# TS-ARM3_0_7.net
KiCad netlist of a schematic drawn in EAGLE
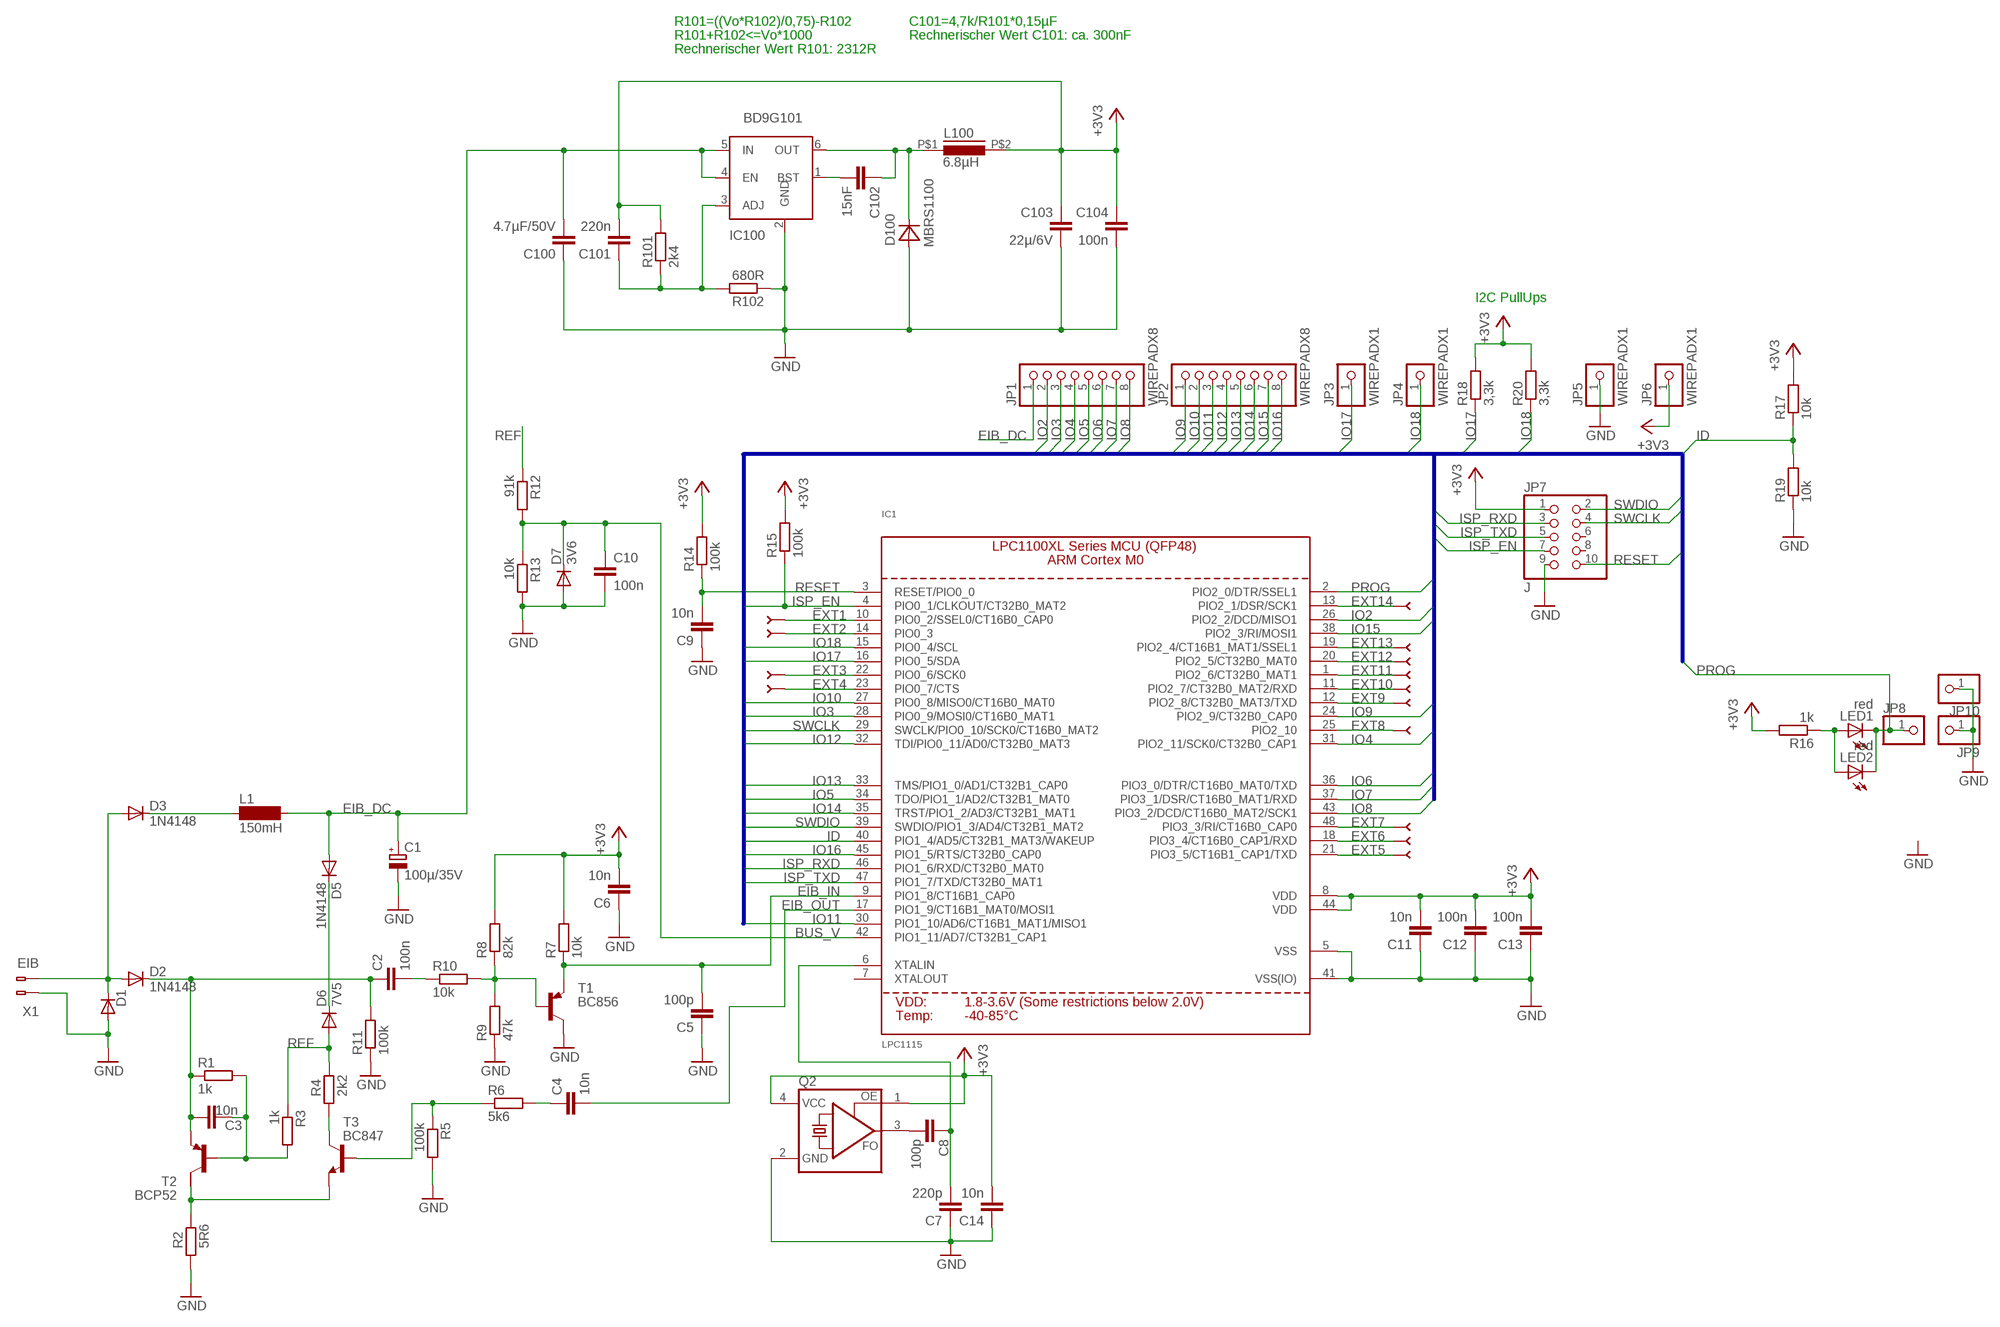
[diagram p0: schematic, sheet 1]

(export (version "E")
  (design (tool "Eeschema 10.0.6"))
  (components
    (comp (ref "C1")
      (value "100µ/35V")
      (footprint "eagle-import:SANYO-OSCON_SMD_C6")
      (libsource (lib "eagle-import") (part "CPOL-EUSANYO_SMD_C6"))
    )
    (comp (ref "C2")
      (value "100n")
      (footprint "eagle-import:C1206")
      (libsource (lib "eagle-import") (part "C-EUC1206"))
    )
    (comp (ref "C3")
      (value "10n")
      (footprint "eagle-import:C1206")
      (libsource (lib "eagle-import") (part "C-EUC1206"))
    )
    (comp (ref "C4")
      (value "10n")
      (footprint "eagle-import:C1206")
      (libsource (lib "eagle-import") (part "C-EUC1206"))
    )
    (comp (ref "C5")
      (value "100p")
      (footprint "eagle-import:C1206")
      (libsource (lib "eagle-import") (part "C-EUC1206"))
    )
    (comp (ref "C6")
      (value "10n")
      (footprint "eagle-import:C1206")
      (libsource (lib "eagle-import") (part "C-EUC1206"))
    )
    (comp (ref "C7")
      (value "220p")
      (footprint "eagle-import:C1206")
      (libsource (lib "eagle-import") (part "C-EUC1206"))
    )
    (comp (ref "C8")
      (value "100p")
      (footprint "eagle-import:C1206")
      (libsource (lib "eagle-import") (part "C-EUC1206"))
    )
    (comp (ref "C9")
      (value "10n")
      (footprint "eagle-import:C1206")
      (libsource (lib "eagle-import") (part "C-EUC1206"))
    )
    (comp (ref "C10")
      (value "100n")
      (footprint "eagle-import:C1206")
      (libsource (lib "eagle-import") (part "C-EUC1206"))
    )
    (comp (ref "C11")
      (value "10n")
      (footprint "eagle-import:C1206")
      (libsource (lib "eagle-import") (part "C-EUC1206"))
    )
    (comp (ref "C12")
      (value "100n")
      (footprint "eagle-import:C1206")
      (libsource (lib "eagle-import") (part "C-EUC1206"))
    )
    (comp (ref "C13")
      (value "100n")
      (footprint "eagle-import:C1206")
      (libsource (lib "eagle-import") (part "C-EUC1206"))
    )
    (comp (ref "C14")
      (value "10n")
      (footprint "eagle-import:C1206")
      (libsource (lib "eagle-import") (part "C-EUC1206"))
    )
    (comp (ref "C100")
      (value "4.7µF/50V")
      (footprint "eagle-import:C1206")
      (libsource (lib "eagle-import") (part "C-EUC1206"))
    )
    (comp (ref "C101")
      (value "220n")
      (footprint "eagle-import:C1206")
      (libsource (lib "eagle-import") (part "C-EUC1206"))
    )
    (comp (ref "C102")
      (value "15nF")
      (footprint "eagle-import:C1206")
      (libsource (lib "eagle-import") (part "C-EUC1206"))
    )
    (comp (ref "C103")
      (value "22µ/6V")
      (footprint "eagle-import:C1206")
      (libsource (lib "eagle-import") (part "C-EUC1206"))
    )
    (comp (ref "C104")
      (value "100n")
      (footprint "eagle-import:C1206")
      (libsource (lib "eagle-import") (part "C-EUC1206"))
    )
    (comp (ref "D1")
      (value "SMAJ40C")
      (footprint "eagle-import:SMB")
      (libsource (lib "eagle-import") (part "D-SMB"))
    )
    (comp (ref "D2")
      (value "1N4148")
      (footprint "eagle-import:MINIMELF")
      (libsource (lib "eagle-import") (part "DIODE-MINIMELF"))
    )
    (comp (ref "D3")
      (value "1N4148")
      (footprint "eagle-import:MINIMELF")
      (libsource (lib "eagle-import") (part "DIODE-MINIMELF"))
    )
    (comp (ref "D5")
      (value "1N4148")
      (footprint "eagle-import:MINIMELF")
      (libsource (lib "eagle-import") (part "DIODE-MINIMELF"))
    )
    (comp (ref "D6")
      (value "7V5")
      (footprint "eagle-import:MINIMELF")
      (libsource (lib "eagle-import") (part "DIODE-MINIMELF"))
    )
    (comp (ref "D7")
      (value "3V6")
      (footprint "eagle-import:MINIMELF")
      (libsource (lib "eagle-import") (part "DIODE-MINIMELF"))
    )
    (comp (ref "D100")
      (value "MBRS1100")
      (footprint "eagle-import:SMA")
      (libsource (lib "eagle-import") (part "MBRA340T3"))
    )
    (comp (ref "IC1")
      (value "LPC1115")
      (footprint "eagle-import:LQFP48")
      (libsource (lib "eagle-import") (part "LPC1113/4/5_QFP48_XLSERIES"))
    )
    (comp (ref "IC100")
      (value "BD9G101")
      (footprint "eagle-import:SOT23-6")
      (libsource (lib "eagle-import") (part "BD9G101GBD9G101G-SOT23-6"))
    )
    (comp (ref "JP1")
      (value "WIREPADX8")
      (footprint "eagle-import:SMD1,27X2,54X8")
      (libsource (lib "eagle-import") (part "WIREPADX8"))
    )
    (comp (ref "JP2")
      (value "WIREPADX8")
      (footprint "eagle-import:SMD1,27X2,54X8")
      (libsource (lib "eagle-import") (part "WIREPADX8"))
    )
    (comp (ref "JP3")
      (value "WIREPADX1")
      (footprint "eagle-import:SMD1,27X2,54")
      (libsource (lib "eagle-import") (part "WIREPADX1"))
    )
    (comp (ref "JP4")
      (value "WIREPADX1")
      (footprint "eagle-import:SMD1,27X2,54")
      (libsource (lib "eagle-import") (part "WIREPADX1"))
    )
    (comp (ref "JP5")
      (value "WIREPADX1")
      (footprint "eagle-import:SMD1,27X2,54")
      (libsource (lib "eagle-import") (part "WIREPADX1"))
    )
    (comp (ref "JP6")
      (value "WIREPADX1")
      (footprint "eagle-import:SMD1,27X2,54")
      (libsource (lib "eagle-import") (part "WIREPADX1"))
    )
    (comp (ref "JP7")
      (value "J")
      (footprint "eagle-import:2X05M")
      (libsource (lib "eagle-import") (part "PINHD-2X05_2.00"))
    )
    (comp (ref "JP8")
      (value "PINHD-1X1")
      (footprint "eagle-import:1X01")
      (libsource (lib "eagle-import") (part "PINHD-1X1"))
    )
    (comp (ref "JP9")
      (value "PINHD-1X1")
      (footprint "eagle-import:1X01")
      (libsource (lib "eagle-import") (part "PINHD-1X1"))
    )
    (comp (ref "JP10")
      (value "PINHD-1X1")
      (footprint "eagle-import:1X01")
      (libsource (lib "eagle-import") (part "PINHD-1X1"))
    )
    (comp (ref "L1")
      (value "150mH")
      (footprint "eagle-import:SD12_1000")
      (libsource (lib "eagle-import") (part "SD12-1000"))
    )
    (comp (ref "L100")
      (value "6.8µH")
      (footprint "eagle-import:PIS2812")
      (libsource (lib "eagle-import") (part "IND_FASTRON_1616FPS"))
    )
    (comp (ref "LED1")
      (value "red")
      (footprint "eagle-import:CHIPLED_1206")
      (libsource (lib "eagle-import") (part "LEDCHIPLED_1206"))
    )
    (comp (ref "LED2")
      (value "red")
      (footprint "eagle-import:LED3MM")
      (libsource (lib "eagle-import") (part "LED3MM"))
    )
    (comp (ref "P1")
      (value "PAD")
      (footprint "eagle-import:PAD")
      (libsource (lib "eagle-import") (part "PAD"))
    )
    (comp (ref "P2")
      (value "PAD")
      (footprint "eagle-import:PAD")
      (libsource (lib "eagle-import") (part "PAD"))
    )
    (comp (ref "P3")
      (value "PAD")
      (footprint "eagle-import:PAD")
      (libsource (lib "eagle-import") (part "PAD"))
    )
    (comp (ref "P4")
      (value "PAD")
      (footprint "eagle-import:PAD")
      (libsource (lib "eagle-import") (part "PAD"))
    )
    (comp (ref "P5")
      (value "PAD")
      (footprint "eagle-import:PAD")
      (libsource (lib "eagle-import") (part "PAD"))
    )
    (comp (ref "P6")
      (value "PAD")
      (footprint "eagle-import:PAD")
      (libsource (lib "eagle-import") (part "PAD"))
    )
    (comp (ref "P7")
      (value "PAD")
      (footprint "eagle-import:PAD")
      (libsource (lib "eagle-import") (part "PAD"))
    )
    (comp (ref "P8")
      (value "PAD")
      (footprint "eagle-import:PAD")
      (libsource (lib "eagle-import") (part "PAD"))
    )
    (comp (ref "P9")
      (value "PAD")
      (footprint "eagle-import:PAD")
      (libsource (lib "eagle-import") (part "PAD"))
    )
    (comp (ref "P10")
      (value "PAD")
      (footprint "eagle-import:PAD")
      (libsource (lib "eagle-import") (part "PAD"))
    )
    (comp (ref "P11")
      (value "PAD")
      (footprint "eagle-import:PAD")
      (libsource (lib "eagle-import") (part "PAD"))
    )
    (comp (ref "P12")
      (value "PAD")
      (footprint "eagle-import:PAD")
      (libsource (lib "eagle-import") (part "PAD"))
    )
    (comp (ref "P13")
      (value "PAD")
      (footprint "eagle-import:PAD")
      (libsource (lib "eagle-import") (part "PAD"))
    )
    (comp (ref "P14")
      (value "PAD")
      (footprint "eagle-import:PAD")
      (libsource (lib "eagle-import") (part "PAD"))
    )
    (comp (ref "Q2")
      (value "ASFL")
      (footprint "eagle-import:ASF")
      (libsource (lib "eagle-import") (part "ASFL"))
    )
    (comp (ref "R1")
      (value "1k")
      (footprint "eagle-import:R1206")
      (libsource (lib "eagle-import") (part "R-EU_R1206"))
    )
    (comp (ref "R2")
      (value "5R6")
      (footprint "eagle-import:R1206")
      (libsource (lib "eagle-import") (part "R-EU_R1206"))
    )
    (comp (ref "R3")
      (value "1k")
      (footprint "eagle-import:R1206")
      (libsource (lib "eagle-import") (part "R-EU_R1206"))
    )
    (comp (ref "R4")
      (value "2k2")
      (footprint "eagle-import:R1206")
      (libsource (lib "eagle-import") (part "R-EU_R1206"))
    )
    (comp (ref "R5")
      (value "100k")
      (footprint "eagle-import:R1206")
      (libsource (lib "eagle-import") (part "R-EU_R1206"))
    )
    (comp (ref "R6")
      (value "5k6")
      (footprint "eagle-import:R1206")
      (libsource (lib "eagle-import") (part "R-EU_R1206"))
    )
    (comp (ref "R7")
      (value "10k")
      (footprint "eagle-import:R1206")
      (libsource (lib "eagle-import") (part "R-EU_R1206"))
    )
    (comp (ref "R8")
      (value "82k")
      (footprint "eagle-import:R1206")
      (libsource (lib "eagle-import") (part "R-EU_R1206"))
    )
    (comp (ref "R9")
      (value "47k")
      (footprint "eagle-import:R1206")
      (libsource (lib "eagle-import") (part "R-EU_R1206"))
    )
    (comp (ref "R10")
      (value "10k")
      (footprint "eagle-import:R1206")
      (libsource (lib "eagle-import") (part "R-EU_R1206"))
    )
    (comp (ref "R11")
      (value "100k")
      (footprint "eagle-import:R1206")
      (libsource (lib "eagle-import") (part "R-EU_R1206"))
    )
    (comp (ref "R12")
      (value "91k")
      (footprint "eagle-import:R1206")
      (libsource (lib "eagle-import") (part "R-EU_R1206"))
    )
    (comp (ref "R13")
      (value "10k")
      (footprint "eagle-import:R1206")
      (libsource (lib "eagle-import") (part "R-EU_R1206"))
    )
    (comp (ref "R14")
      (value "100k")
      (footprint "eagle-import:R1206")
      (libsource (lib "eagle-import") (part "R-EU_R1206"))
    )
    (comp (ref "R15")
      (value "100k")
      (footprint "eagle-import:R1206")
      (libsource (lib "eagle-import") (part "R-EU_R1206"))
    )
    (comp (ref "R16")
      (value "1k")
      (footprint "eagle-import:R1206")
      (libsource (lib "eagle-import") (part "R-EU_R1206"))
    )
    (comp (ref "R17")
      (value "10k")
      (footprint "eagle-import:R1206")
      (libsource (lib "eagle-import") (part "R-EU_R1206"))
    )
    (comp (ref "R18")
      (value "3,3k")
      (footprint "eagle-import:R1206")
      (libsource (lib "eagle-import") (part "R-EU_R1206"))
    )
    (comp (ref "R19")
      (value "10k")
      (footprint "eagle-import:R1206")
      (libsource (lib "eagle-import") (part "R-EU_R1206"))
    )
    (comp (ref "R20")
      (value "3,3k")
      (footprint "eagle-import:R1206")
      (libsource (lib "eagle-import") (part "R-EU_R1206"))
    )
    (comp (ref "R101")
      (value "2k4")
      (footprint "eagle-import:R1206")
      (libsource (lib "eagle-import") (part "R-EU_R1206"))
    )
    (comp (ref "R102")
      (value "680R")
      (footprint "eagle-import:R1206")
      (libsource (lib "eagle-import") (part "R-EU_R1206"))
    )
    (comp (ref "T1")
      (value "BC856")
      (footprint "eagle-import:SOT23-BEC")
      (libsource (lib "eagle-import") (part "BC856SMDB"))
    )
    (comp (ref "T2")
      (value "BCP52")
      (footprint "eagle-import:SOT223")
      (libsource (lib "eagle-import") (part "FZT753SMD"))
    )
    (comp (ref "T3")
      (value "BC847")
      (footprint "eagle-import:SOT23")
      (libsource (lib "eagle-import") (part "BC847"))
    )
    (comp (ref "X1")
      (value "EIB")
      (footprint "eagle-import:BUSKLEMME243-724")
      (libsource (lib "eagle-import") (part "EIB"))
    )
  )
  (nets
    (net (code "1") (name "+3V3") (class "Default")
      (node (ref "C101") (pin "2") (pinfunction "2_2") (pintype "passive"))
      (node (ref "C103") (pin "1") (pinfunction "1_1") (pintype "passive"))
      (node (ref "C104") (pin "1") (pinfunction "1_1") (pintype "passive"))
      (node (ref "C11") (pin "2") (pinfunction "2_2") (pintype "passive"))
      (node (ref "C12") (pin "2") (pinfunction "2_2") (pintype "passive"))
      (node (ref "C13") (pin "2") (pinfunction "2_2") (pintype "passive"))
      (node (ref "C14") (pin "2") (pinfunction "2_2") (pintype "passive"))
      (node (ref "C6") (pin "2") (pinfunction "2_2") (pintype "passive"))
      (node (ref "IC1") (pin "44") (pinfunction "VDD_44") (pintype "power_in"))
      (node (ref "IC1") (pin "8") (pinfunction "VDD_8") (pintype "power_in"))
      (node (ref "JP6") (pin "1") (pinfunction "1_1") (pintype "passive"))
      (node (ref "JP7") (pin "1") (pinfunction "1_1") (pintype "passive"))
      (node (ref "L100") (pin "P$2") (pinfunction "2_P$2") (pintype "passive"))
      (node (ref "Q2") (pin "1") (pinfunction "OE_1") (pintype "input"))
      (node (ref "Q2") (pin "4") (pinfunction "VCC_4") (pintype "power_in"))
      (node (ref "R101") (pin "2") (pinfunction "2_2") (pintype "passive"))
      (node (ref "R14") (pin "2") (pinfunction "2_2") (pintype "passive"))
      (node (ref "R15") (pin "2") (pinfunction "2_2") (pintype "passive"))
      (node (ref "R16") (pin "2") (pinfunction "2_2") (pintype "passive"))
      (node (ref "R17") (pin "2") (pinfunction "2_2") (pintype "passive"))
      (node (ref "R18") (pin "2") (pinfunction "2_2") (pintype "passive"))
      (node (ref "R20") (pin "2") (pinfunction "2_2") (pintype "passive"))
      (node (ref "R7") (pin "2") (pinfunction "2_2") (pintype "passive"))
      (node (ref "R8") (pin "2") (pinfunction "2_2") (pintype "passive"))
    )
    (net (code "2") (name "/BUS_V") (class "Default")
      (node (ref "C10") (pin "2") (pinfunction "2_2") (pintype "passive"))
      (node (ref "D7") (pin "C") (pinfunction "C_C") (pintype "passive"))
      (node (ref "IC1") (pin "42") (pinfunction "PIO1_11/AD7/CT32B1_CAP1_42") (pintype "bidirectional"))
      (node (ref "R12") (pin "2") (pinfunction "2_2") (pintype "passive"))
      (node (ref "R13") (pin "1") (pinfunction "1_1") (pintype "passive"))
    )
    (net (code "3") (name "/EIB_DC") (class "Default")
      (node (ref "C1") (pin "+") (pinfunction "+_+") (pintype "passive"))
      (node (ref "C100") (pin "2") (pinfunction "2_2") (pintype "passive"))
      (node (ref "D5") (pin "A") (pinfunction "A_A") (pintype "passive"))
      (node (ref "IC100") (pin "4") (pinfunction "EN_4") (pintype "input"))
      (node (ref "IC100") (pin "5") (pinfunction "IN_5") (pintype "input"))
      (node (ref "JP1") (pin "1") (pinfunction "1_1") (pintype "passive"))
      (node (ref "L1") (pin "2") (pinfunction "2_2") (pintype "passive"))
    )
    (net (code "4") (name "/EIB_IN") (class "Default")
      (node (ref "C5") (pin "2") (pinfunction "2_2") (pintype "passive"))
      (node (ref "IC1") (pin "9") (pinfunction "PIO1_8/CT16B1_CAP0_9") (pintype "bidirectional"))
      (node (ref "R7") (pin "1") (pinfunction "1_1") (pintype "passive"))
      (node (ref "T1") (pin "E") (pinfunction "E_E") (pintype "passive"))
    )
    (net (code "5") (name "/EIB_OUT") (class "Default")
      (node (ref "C4") (pin "2") (pinfunction "2_2") (pintype "passive"))
      (node (ref "IC1") (pin "17") (pinfunction "PIO1_9/CT16B1_MAT0/MOSI1_17") (pintype "bidirectional"))
    )
    (net (code "6") (name "/EXT1") (class "Default")
      (node (ref "IC1") (pin "10") (pinfunction "PIO0_2/SSEL0/CT16B0_CAP0_10") (pintype "bidirectional"))
      (node (ref "P1") (pin "1") (pinfunction "1_1") (pintype "bidirectional"))
    )
    (net (code "7") (name "/EXT2") (class "Default")
      (node (ref "IC1") (pin "14") (pinfunction "PIO0_3_14") (pintype "bidirectional"))
      (node (ref "P2") (pin "1") (pinfunction "1_1") (pintype "bidirectional"))
    )
    (net (code "8") (name "/EXT3") (class "Default")
      (node (ref "IC1") (pin "22") (pinfunction "PIO0_6/SCK0_22") (pintype "bidirectional"))
      (node (ref "P13") (pin "1") (pinfunction "1_1") (pintype "bidirectional"))
    )
    (net (code "9") (name "/EXT4") (class "Default")
      (node (ref "IC1") (pin "23") (pinfunction "PIO0_7/CTS_23") (pintype "bidirectional"))
      (node (ref "P14") (pin "1") (pinfunction "1_1") (pintype "bidirectional"))
    )
    (net (code "10") (name "/EXT5") (class "Default")
      (node (ref "IC1") (pin "21") (pinfunction "PIO3_5/CT16B1_CAP1/TXD_21") (pintype "bidirectional"))
      (node (ref "P12") (pin "1") (pinfunction "1_1") (pintype "bidirectional"))
    )
    (net (code "11") (name "/EXT6") (class "Default")
      (node (ref "IC1") (pin "18") (pinfunction "PIO3_4/CT16B0_CAP1/RXD_18") (pintype "bidirectional"))
      (node (ref "P11") (pin "1") (pinfunction "1_1") (pintype "bidirectional"))
    )
    (net (code "12") (name "/EXT7") (class "Default")
      (node (ref "IC1") (pin "48") (pinfunction "PIO3_3/RI/CT16B0_CAP0_48") (pintype "bidirectional"))
      (node (ref "P10") (pin "1") (pinfunction "1_1") (pintype "bidirectional"))
    )
    (net (code "13") (name "/EXT8") (class "Default")
      (node (ref "IC1") (pin "25") (pinfunction "PIO2_10_25") (pintype "bidirectional"))
      (node (ref "P6") (pin "1") (pinfunction "1_1") (pintype "bidirectional"))
    )
    (net (code "14") (name "/EXT9") (class "Default")
      (node (ref "IC1") (pin "12") (pinfunction "PIO2_8/CT32B0_MAT3/TXD_12") (pintype "bidirectional"))
      (node (ref "P4") (pin "1") (pinfunction "1_1") (pintype "bidirectional"))
    )
    (net (code "15") (name "/EXT10") (class "Default")
      (node (ref "IC1") (pin "11") (pinfunction "PIO2_7/CT32B0_MAT2/RXD_11") (pintype "bidirectional"))
      (node (ref "P5") (pin "1") (pinfunction "1_1") (pintype "bidirectional"))
    )
    (net (code "16") (name "/EXT11") (class "Default")
      (node (ref "IC1") (pin "1") (pinfunction "PIO2_6/CT32B0_MAT1_1") (pintype "bidirectional"))
      (node (ref "P9") (pin "1") (pinfunction "1_1") (pintype "bidirectional"))
    )
    (net (code "17") (name "/EXT12") (class "Default")
      (node (ref "IC1") (pin "20") (pinfunction "PIO2_5/CT32B0_MAT0_20") (pintype "bidirectional"))
      (node (ref "P8") (pin "1") (pinfunction "1_1") (pintype "bidirectional"))
    )
    (net (code "18") (name "/EXT13") (class "Default")
      (node (ref "IC1") (pin "19") (pinfunction "PIO2_4/CT16B1_MAT1/SSEL1_19") (pintype "bidirectional"))
      (node (ref "P7") (pin "1") (pinfunction "1_1") (pintype "bidirectional"))
    )
    (net (code "19") (name "/EXT14") (class "Default")
      (node (ref "IC1") (pin "13") (pinfunction "PIO2_1/DSR/SCK1_13") (pintype "bidirectional"))
      (node (ref "P3") (pin "1") (pinfunction "1_1") (pintype "bidirectional"))
    )
    (net (code "20") (name "/ID") (class "Default")
      (node (ref "IC1") (pin "40") (pinfunction "PIO1_4/AD5/CT32B1_MAT3/WAKEUP_40") (pintype "bidirectional"))
      (node (ref "R17") (pin "1") (pinfunction "1_1") (pintype "passive"))
      (node (ref "R19") (pin "2") (pinfunction "2_2") (pintype "passive"))
    )
    (net (code "21") (name "/IO2") (class "Default")
      (node (ref "IC1") (pin "26") (pinfunction "PIO2_2/DCD/MISO1_26") (pintype "bidirectional"))
      (node (ref "JP1") (pin "2") (pinfunction "2_2") (pintype "passive"))
    )
    (net (code "22") (name "/IO3") (class "Default")
      (node (ref "IC1") (pin "28") (pinfunction "PIO0_9/MOSI0/CT16B0_MAT1_28") (pintype "bidirectional"))
      (node (ref "JP1") (pin "3") (pinfunction "3_3") (pintype "passive"))
    )
    (net (code "23") (name "/IO4") (class "Default")
      (node (ref "IC1") (pin "31") (pinfunction "PIO2_11/SCK0/CT32B0_CAP1_31") (pintype "bidirectional"))
      (node (ref "JP1") (pin "4") (pinfunction "4_4") (pintype "passive"))
    )
    (net (code "24") (name "/IO5") (class "Default")
      (node (ref "IC1") (pin "34") (pinfunction "TDO/PIO1_1/AD2/CT32B1_MAT0_34") (pintype "bidirectional"))
      (node (ref "JP1") (pin "5") (pinfunction "5_5") (pintype "passive"))
    )
    (net (code "25") (name "/IO6") (class "Default")
      (node (ref "IC1") (pin "36") (pinfunction "PIO3_0/DTR/CT16B0_MAT0/TXD_36") (pintype "bidirectional"))
      (node (ref "JP1") (pin "6") (pinfunction "6_6") (pintype "passive"))
    )
    (net (code "26") (name "/IO7") (class "Default")
      (node (ref "IC1") (pin "37") (pinfunction "PIO3_1/DSR/CT16B0_MAT1/RXD_37") (pintype "bidirectional"))
      (node (ref "JP1") (pin "7") (pinfunction "7_7") (pintype "passive"))
    )
    (net (code "27") (name "/IO8") (class "Default")
      (node (ref "IC1") (pin "43") (pinfunction "PIO3_2/DCD/CT16B0_MAT2/SCK1_43") (pintype "bidirectional"))
      (node (ref "JP1") (pin "8") (pinfunction "8_8") (pintype "passive"))
    )
    (net (code "28") (name "/IO9") (class "Default")
      (node (ref "IC1") (pin "24") (pinfunction "PIO2_9/CT32B0_CAP0_24") (pintype "bidirectional"))
      (node (ref "JP2") (pin "1") (pinfunction "1_1") (pintype "passive"))
    )
    (net (code "29") (name "/IO10") (class "Default")
      (node (ref "IC1") (pin "27") (pinfunction "PIO0_8/MISO0/CT16B0_MAT0_27") (pintype "bidirectional"))
      (node (ref "JP2") (pin "2") (pinfunction "2_2") (pintype "passive"))
    )
    (net (code "30") (name "/IO11") (class "Default")
      (node (ref "IC1") (pin "30") (pinfunction "PIO1_10/AD6/CT16B1_MAT1/MISO1_30") (pintype "bidirectional"))
      (node (ref "JP2") (pin "3") (pinfunction "3_3") (pintype "passive"))
    )
    (net (code "31") (name "/IO12") (class "Default")
      (node (ref "IC1") (pin "32") (pinfunction "TDI/PIO0_11/AD0/CT32B0_MAT3_32") (pintype "bidirectional"))
      (node (ref "JP2") (pin "4") (pinfunction "4_4") (pintype "passive"))
    )
    (net (code "32") (name "/IO13") (class "Default")
      (node (ref "IC1") (pin "33") (pinfunction "TMS/PIO1_0/AD1/CT32B1_CAP0_33") (pintype "bidirectional"))
      (node (ref "JP2") (pin "5") (pinfunction "5_5") (pintype "passive"))
    )
    (net (code "33") (name "/IO14") (class "Default")
      (node (ref "IC1") (pin "35") (pinfunction "TRST/PIO1_2/AD3/CT32B1_MAT1_35") (pintype "bidirectional"))
      (node (ref "JP2") (pin "6") (pinfunction "6_6") (pintype "passive"))
    )
    (net (code "34") (name "/IO15") (class "Default")
      (node (ref "IC1") (pin "38") (pinfunction "PIO2_3/RI/MOSI1_38") (pintype "bidirectional"))
      (node (ref "JP2") (pin "7") (pinfunction "7_7") (pintype "passive"))
    )
    (net (code "35") (name "/IO16") (class "Default")
      (node (ref "IC1") (pin "45") (pinfunction "PIO1_5/RTS/CT32B0_CAP0_45") (pintype "bidirectional"))
      (node (ref "JP2") (pin "8") (pinfunction "8_8") (pintype "passive"))
    )
    (net (code "36") (name "/IO17") (class "Default")
      (node (ref "IC1") (pin "16") (pinfunction "PIO0_5/SDA_16") (pintype "bidirectional"))
      (node (ref "JP3") (pin "1") (pinfunction "1_1") (pintype "passive"))
      (node (ref "R18") (pin "1") (pinfunction "1_1") (pintype "passive"))
    )
    (net (code "37") (name "/IO18") (class "Default")
      (node (ref "IC1") (pin "15") (pinfunction "PIO0_4/SCL_15") (pintype "bidirectional"))
      (node (ref "JP4") (pin "1") (pinfunction "1_1") (pintype "passive"))
      (node (ref "R20") (pin "1") (pinfunction "1_1") (pintype "passive"))
    )
    (net (code "38") (name "/ISP_EN") (class "Default")
      (node (ref "IC1") (pin "4") (pinfunction "PIO0_1/CLKOUT/CT32B0_MAT2_4") (pintype "bidirectional"))
      (node (ref "JP7") (pin "7") (pinfunction "7_7") (pintype "passive"))
      (node (ref "R15") (pin "1") (pinfunction "1_1") (pintype "passive"))
    )
    (net (code "39") (name "/ISP_RXD") (class "Default")
      (node (ref "IC1") (pin "46") (pinfunction "PIO1_6/RXD/CT32B0_MAT0_46") (pintype "bidirectional"))
      (node (ref "JP7") (pin "3") (pinfunction "3_3") (pintype "passive"))
    )
    (net (code "40") (name "/ISP_TXD") (class "Default")
      (node (ref "IC1") (pin "47") (pinfunction "PIO1_7/TXD/CT32B0_MAT1_47") (pintype "bidirectional"))
      (node (ref "JP7") (pin "5") (pinfunction "5_5") (pintype "passive"))
    )
    (net (code "41") (name "/PROG") (class "Default")
      (node (ref "IC1") (pin "2") (pinfunction "PIO2_0/DTR/SSEL1_2") (pintype "bidirectional"))
      (node (ref "JP8") (pin "1") (pinfunction "1_1") (pintype "passive"))
      (node (ref "LED1") (pin "C") (pinfunction "C_C") (pintype "passive"))
      (node (ref "LED2") (pin "K") (pinfunction "C_K") (pintype "passive"))
    )
    (net (code "42") (name "/REF") (class "Default")
      (node (ref "D6") (pin "A") (pinfunction "A_A") (pintype "passive"))
      (node (ref "R12") (pin "1") (pinfunction "1_1") (pintype "passive"))
      (node (ref "R3") (pin "1") (pinfunction "1_1") (pintype "passive"))
      (node (ref "R4") (pin "2") (pinfunction "2_2") (pintype "passive"))
    )
    (net (code "43") (name "/RESET") (class "Default")
      (node (ref "C9") (pin "2") (pinfunction "2_2") (pintype "passive"))
      (node (ref "IC1") (pin "3") (pinfunction "RESET/PIO0_0_3") (pintype "bidirectional"))
      (node (ref "JP7") (pin "10") (pinfunction "10_10") (pintype "passive"))
      (node (ref "R14") (pin "1") (pinfunction "1_1") (pintype "passive"))
    )
    (net (code "44") (name "/SWCLK") (class "Default")
      (node (ref "IC1") (pin "29") (pinfunction "SWCLK/PIO0_10/SCK0/CT16B0_MAT2_29") (pintype "bidirectional"))
      (node (ref "JP7") (pin "4") (pinfunction "4_4") (pintype "passive"))
    )
    (net (code "45") (name "/SWDIO") (class "Default")
      (node (ref "IC1") (pin "39") (pinfunction "SWDIO/PIO1_3/AD4/CT32B1_MAT2_39") (pintype "bidirectional"))
      (node (ref "JP7") (pin "2") (pinfunction "2_2") (pintype "passive"))
    )
    (net (code "46") (name "GND") (class "Default")
      (node (ref "C1") (pin "-") (pinfunction "-_-") (pintype "passive"))
      (node (ref "C10") (pin "1") (pinfunction "1_1") (pintype "passive"))
      (node (ref "C100") (pin "1") (pinfunction "1_1") (pintype "passive"))
      (node (ref "C103") (pin "2") (pinfunction "2_2") (pintype "passive"))
      (node (ref "C104") (pin "2") (pinfunction "2_2") (pintype "passive"))
      (node (ref "C11") (pin "1") (pinfunction "1_1") (pintype "passive"))
      (node (ref "C12") (pin "1") (pinfunction "1_1") (pintype "passive"))
      (node (ref "C13") (pin "1") (pinfunction "1_1") (pintype "passive"))
      (node (ref "C14") (pin "1") (pinfunction "1_1") (pintype "passive"))
      (node (ref "C5") (pin "1") (pinfunction "1_1") (pintype "passive"))
      (node (ref "C6") (pin "1") (pinfunction "1_1") (pintype "passive"))
      (node (ref "C7") (pin "1") (pinfunction "1_1") (pintype "passive"))
      (node (ref "C9") (pin "1") (pinfunction "1_1") (pintype "passive"))
      (node (ref "D1") (pin "2") (pinfunction "A_2") (pintype "passive"))
      (node (ref "D100") (pin "A") (pinfunction "A_A") (pintype "passive"))
      (node (ref "D7") (pin "A") (pinfunction "A_A") (pintype "passive"))
      (node (ref "IC1") (pin "41") (pinfunction "VSS(IO)_41") (pintype "power_in"))
      (node (ref "IC1") (pin "5") (pinfunction "VSS_5") (pintype "power_in"))
      (node (ref "IC100") (pin "2") (pinfunction "GND_2") (pintype "power_in"))
      (node (ref "JP10") (pin "1") (pinfunction "1_1") (pintype "passive"))
      (node (ref "JP5") (pin "1") (pinfunction "1_1") (pintype "passive"))
      (node (ref "JP7") (pin "9") (pinfunction "9_9") (pintype "passive"))
      (node (ref "JP9") (pin "1") (pinfunction "1_1") (pintype "passive"))
      (node (ref "Q2") (pin "2") (pinfunction "GND_2") (pintype "power_in"))
      (node (ref "R102") (pin "1") (pinfunction "1_1") (pintype "passive"))
      (node (ref "R11") (pin "1") (pinfunction "1_1") (pintype "passive"))
      (node (ref "R13") (pin "2") (pinfunction "2_2") (pintype "passive"))
      (node (ref "R19") (pin "1") (pinfunction "1_1") (pintype "passive"))
      (node (ref "R2") (pin "1") (pinfunction "1_1") (pintype "passive"))
      (node (ref "R5") (pin "2") (pinfunction "2_2") (pintype "passive"))
      (node (ref "R9") (pin "1") (pinfunction "1_1") (pintype "passive"))
      (node (ref "T1") (pin "C") (pinfunction "C_C") (pintype "passive"))
      (node (ref "X1") (pin "1") (pinfunction "B-1_1") (pintype "passive"))
    )
    (net (code "47") (name "Net-(C2-Pad2)") (class "Default")
      (node (ref "C2") (pin "2") (pinfunction "2_2") (pintype "passive"))
      (node (ref "R10") (pin "1") (pinfunction "1_1") (pintype "passive"))
    )
    (net (code "48") (name "Net-(C4-Pad1)") (class "Default")
      (node (ref "C4") (pin "1") (pinfunction "1_1") (pintype "passive"))
      (node (ref "R6") (pin "2") (pinfunction "2_2") (pintype "passive"))
    )
    (net (code "49") (name "Net-(D1-C)") (class "Default")
      (node (ref "D1") (pin "1") (pinfunction "C_1") (pintype "passive"))
      (node (ref "D2") (pin "A") (pinfunction "A_A") (pintype "passive"))
      (node (ref "D3") (pin "A") (pinfunction "A_A") (pintype "passive"))
      (node (ref "X1") (pin "2") (pinfunction "B-2_2") (pintype "passive"))
    )
    (net (code "50") (name "Net-(D3-PadC)") (class "Default")
      (node (ref "D3") (pin "C") (pinfunction "C_C") (pintype "passive"))
      (node (ref "L1") (pin "1") (pinfunction "1_1") (pintype "passive"))
    )
    (net (code "51") (name "Net-(D5-PadC)") (class "Default")
      (node (ref "D5") (pin "C") (pinfunction "C_C") (pintype "passive"))
      (node (ref "D6") (pin "C") (pinfunction "C_C") (pintype "passive"))
    )
    (net (code "52") (name "Net-(IC1-XTALIN)") (class "Default")
      (node (ref "C7") (pin "2") (pinfunction "2_2") (pintype "passive"))
      (node (ref "C8") (pin "1") (pinfunction "1_1") (pintype "passive"))
      (node (ref "IC1") (pin "6") (pinfunction "XTALIN_6") (pintype "input"))
    )
    (net (code "53") (name "Net-(IC100-ADJ)") (class "Default")
      (node (ref "C101") (pin "1") (pinfunction "1_1") (pintype "passive"))
      (node (ref "IC100") (pin "3") (pinfunction "ADJ_3") (pintype "passive"))
      (node (ref "R101") (pin "1") (pinfunction "1_1") (pintype "passive"))
      (node (ref "R102") (pin "2") (pinfunction "2_2") (pintype "passive"))
    )
    (net (code "54") (name "Net-(IC100-BST)") (class "Default")
      (node (ref "C102") (pin "2") (pinfunction "2_2") (pintype "passive"))
      (node (ref "IC100") (pin "1") (pinfunction "BST_1") (pintype "output"))
    )
    (net (code "55") (name "Net-(IC100-OUT)") (class "Default")
      (node (ref "C102") (pin "1") (pinfunction "1_1") (pintype "passive"))
      (node (ref "D100") (pin "C") (pinfunction "C_C") (pintype "passive"))
      (node (ref "IC100") (pin "6") (pinfunction "OUT_6") (pintype "output"))
      (node (ref "L100") (pin "P$1") (pinfunction "1_P$1") (pintype "passive"))
    )
    (net (code "56") (name "Net-(LED1-PadA)") (class "Default")
      (node (ref "LED1") (pin "A") (pinfunction "A_A") (pintype "passive"))
      (node (ref "LED2") (pin "A") (pinfunction "A_A") (pintype "passive"))
      (node (ref "R16") (pin "1") (pinfunction "1_1") (pintype "passive"))
    )
    (net (code "57") (name "Net-(Q2-FO)") (class "Default")
      (node (ref "C8") (pin "2") (pinfunction "2_2") (pintype "passive"))
      (node (ref "Q2") (pin "3") (pinfunction "FO_3") (pintype "output"))
    )
    (net (code "58") (name "Net-(R10-Pad2)") (class "Default")
      (node (ref "R10") (pin "2") (pinfunction "2_2") (pintype "passive"))
      (node (ref "R8") (pin "1") (pinfunction "1_1") (pintype "passive"))
      (node (ref "R9") (pin "2") (pinfunction "2_2") (pintype "passive"))
      (node (ref "T1") (pin "B") (pinfunction "B_B") (pintype "passive"))
    )
    (net (code "59") (name "Net-(T2-B)") (class "Default")
      (node (ref "C3") (pin "2") (pinfunction "2_2") (pintype "passive"))
      (node (ref "R1") (pin "2") (pinfunction "2_2") (pintype "passive"))
      (node (ref "R3") (pin "2") (pinfunction "2_2") (pintype "passive"))
      (node (ref "T2") (pin "1") (pinfunction "B_1") (pintype "passive"))
    )
    (net (code "60") (name "Net-(T2-C)") (class "Default")
      (node (ref "R2") (pin "2") (pinfunction "2_2") (pintype "passive"))
      (node (ref "T2") (pin "2") (pinfunction "C_2") (pintype "passive"))
      (node (ref "T3") (pin "2") (pinfunction "E_2") (pintype "passive"))
    )
    (net (code "61") (name "Net-(T2-E)") (class "Default")
      (node (ref "C2") (pin "1") (pinfunction "1_1") (pintype "passive"))
      (node (ref "C3") (pin "1") (pinfunction "1_1") (pintype "passive"))
      (node (ref "D2") (pin "C") (pinfunction "C_C") (pintype "passive"))
      (node (ref "R1") (pin "1") (pinfunction "1_1") (pintype "passive"))
      (node (ref "R11") (pin "2") (pinfunction "2_2") (pintype "passive"))
      (node (ref "T2") (pin "3") (pinfunction "E_3") (pintype "passive"))
    )
    (net (code "62") (name "Net-(T3-B)") (class "Default")
      (node (ref "R5") (pin "1") (pinfunction "1_1") (pintype "passive"))
      (node (ref "R6") (pin "1") (pinfunction "1_1") (pintype "passive"))
      (node (ref "T3") (pin "1") (pinfunction "B_1") (pintype "passive"))
    )
    (net (code "63") (name "Net-(T3-C)") (class "Default")
      (node (ref "R4") (pin "1") (pinfunction "1_1") (pintype "passive"))
      (node (ref "T3") (pin "3") (pinfunction "C_3") (pintype "passive"))
    )
    (net (code "64") (name "unconnected-(IC1-XTALOUT-Pad7)") (class "Default")
      (node (ref "IC1") (pin "7") (pinfunction "XTALOUT_7") (pintype "output"))
    )
    (net (code "65") (name "unconnected-(JP7-Pad6)") (class "Default")
      (node (ref "JP7") (pin "6") (pinfunction "6_6") (pintype "passive"))
    )
    (net (code "66") (name "unconnected-(JP7-Pad8)") (class "Default")
      (node (ref "JP7") (pin "8") (pinfunction "8_8") (pintype "passive"))
    )
    (net (code "67") (name "unconnected-(T2-C{slash}-Pad4)") (class "Default")
      (node (ref "T2") (pin "4") (pinfunction "C/_4") (pintype "passive"))
    )
  )
)
